# VoltageRegulator_3v3.net
KiCad netlist of a schematic drawn in Altium Designer
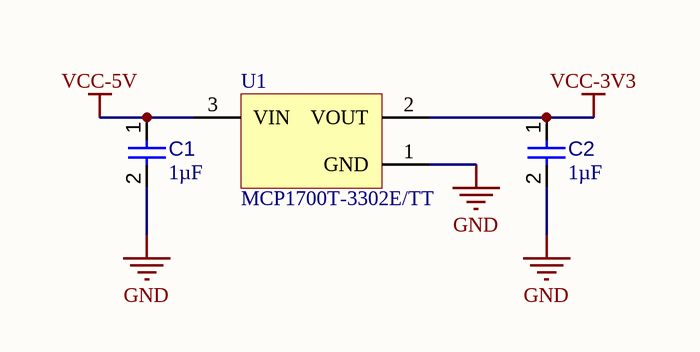
[diagram p0: VoltageRegulator_3v3.SchDoc]

(export (version "E")
  (design (tool "Eeschema 10.0.6"))
  (components
    (comp (ref "C1")
      (value "1µF")
      (footprint "CAPC0603(1608)100_L")
      (description "Chip Capacitor, 1µF +/-40%, 50V, 0603, Thickness 1 mm")
      (fields (field (name "TOLERANCE") "10%") (field (name "Comment") "Capacitor 1µF +/-40% 50V 0603"))
      (libsource (lib "RUR") (part "CAP-NP-2"))
    )
    (comp (ref "C2")
      (value "1µF")
      (footprint "CAPC0603(1608)100_L")
      (description "Chip Capacitor, 1µF +/-40%, 50V, 0603, Thickness 1 mm")
      (fields (field (name "TOLERANCE") "10%") (field (name "Comment") "Capacitor 1µF +/-40% 50V 0603"))
      (libsource (lib "RUR") (part "CAP-NP-2"))
    )
    (comp (ref "U1")
      (value "MCP1700T-3302E/TT")
      (footprint "SOT-23-TT3_N")
      (description "Low Quiescent Current LDO, 3-Pin SOT-23, Extended Temperature, Tape and Reel")
      (libsource (lib "Altium Content Vault") (part "PM-LINEREG-MCP1700-IL3"))
    )
  )
  (nets
    (net (code "1") (name "GND") (class "Default")
      (node (ref "C1") (pin "2") (pinfunction "2_2") (pintype "passive"))
      (node (ref "C2") (pin "2") (pinfunction "2_2") (pintype "passive"))
      (node (ref "U1") (pin "1") (pinfunction "GND_1") (pintype "power_in"))
    )
    (net (code "2") (name "VCC-3V3") (class "Default")
      (node (ref "C2") (pin "1") (pinfunction "1_1") (pintype "passive"))
      (node (ref "U1") (pin "2") (pinfunction "VOUT_2") (pintype "power_in"))
    )
    (net (code "3") (name "VCC-5V") (class "Default")
      (node (ref "C1") (pin "1") (pinfunction "1_1") (pintype "passive"))
      (node (ref "U1") (pin "3") (pinfunction "VIN_3") (pintype "power_in"))
    )
  )
)
